# satshakit_FabPCBMaker.net
KiCad netlist of a schematic drawn in EAGLE
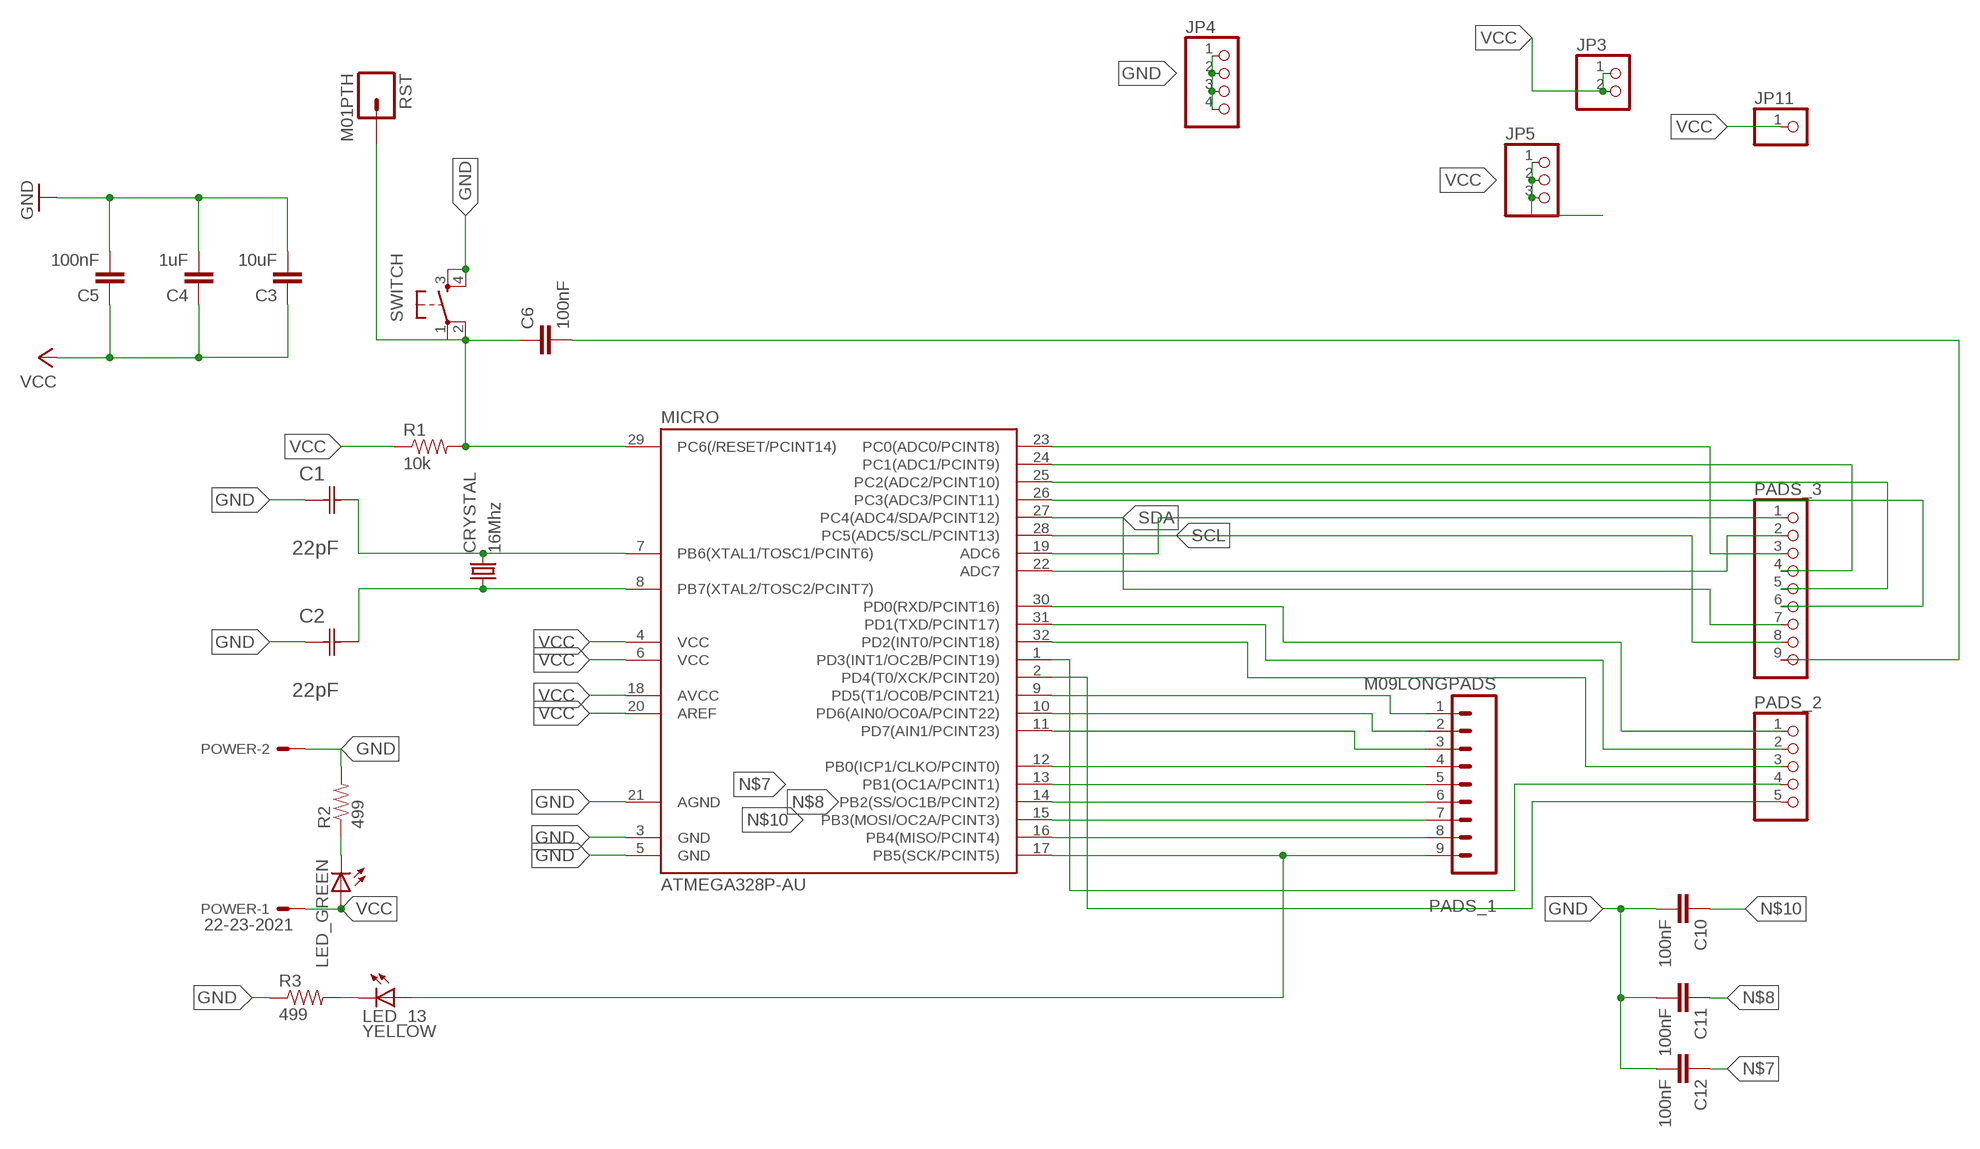
[diagram p0: schematic, sheet 1]

(export (version "E")
  (design (tool "Eeschema 10.0.6"))
  (components
    (comp (ref "C1")
      (value "22pF")
      (footprint "eagle-import:CAPC3216X178N")
      (fields (field (name "MPN") "0612ZC225MAT2A") (field (name "TOLERANCE") "±20%"))
      (libsource (lib "eagle-import") (part "0612ZC225MAT2A"))
    )
    (comp (ref "C2")
      (value "22pF")
      (footprint "eagle-import:CAPC3216X178N")
      (fields (field (name "MPN") "0612ZC225MAT2A") (field (name "TOLERANCE") "±20%"))
      (libsource (lib "eagle-import") (part "0612ZC225MAT2A"))
    )
    (comp (ref "C3")
      (value "10uF")
      (footprint "eagle-import:1206")
      (libsource (lib "eagle-import") (part "CAP1206"))
    )
    (comp (ref "C4")
      (value "1uF")
      (footprint "eagle-import:1206")
      (libsource (lib "eagle-import") (part "CAP1206"))
    )
    (comp (ref "C5")
      (value "100nF")
      (footprint "eagle-import:1206")
      (libsource (lib "eagle-import") (part "CAP1206"))
    )
    (comp (ref "C6")
      (value "100nF")
      (footprint "eagle-import:1206")
      (libsource (lib "eagle-import") (part "CAP1206"))
    )
    (comp (ref "C10")
      (value "100nF")
      (footprint "eagle-import:1206")
      (libsource (lib "eagle-import") (part "CAP1206"))
    )
    (comp (ref "C11")
      (value "100nF")
      (footprint "eagle-import:1206")
      (libsource (lib "eagle-import") (part "CAP1206"))
    )
    (comp (ref "C12")
      (value "100nF")
      (footprint "eagle-import:1206")
      (libsource (lib "eagle-import") (part "CAP1206"))
    )
    (comp (ref "CRYSTAL")
      (value "16Mhz")
      (footprint "eagle-import:CSM-7X-DU")
      (libsource (lib "eagle-import") (part "CSM-7X-DU"))
    )
    (comp (ref "JP3")
      (value "PINHD-1X2")
      (footprint "eagle-import:1X02")
      (libsource (lib "eagle-import") (part "PINHD-1X2"))
    )
    (comp (ref "JP4")
      (value "PINHD-1X4")
      (footprint "eagle-import:1X04")
      (libsource (lib "eagle-import") (part "PINHD-1X4"))
    )
    (comp (ref "JP5")
      (value "PINHD-1X3")
      (footprint "eagle-import:1X03")
      (libsource (lib "eagle-import") (part "PINHD-1X3"))
    )
    (comp (ref "JP11")
      (value "PINHD-1X1")
      (footprint "eagle-import:1X01")
      (libsource (lib "eagle-import") (part "PINHD-1X1"))
    )
    (comp (ref "LED_13")
      (value "YELLOW")
      (footprint "eagle-import:1206")
      (libsource (lib "eagle-import") (part "LED1206"))
    )
    (comp (ref "LED_GREEN")
      (value "LED1206")
      (footprint "eagle-import:1206")
      (libsource (lib "eagle-import") (part "LED1206"))
    )
    (comp (ref "MICRO")
      (value "ATMEGA328P-AU")
      (footprint "eagle-import:TQFP32-08")
      (libsource (lib "eagle-import") (part "ATMEGA48/88/168-AU"))
    )
    (comp (ref "PADS_1")
      (value "M09LONGPADS")
      (footprint "eagle-import:1X09_LONGPADS")
      (libsource (lib "eagle-import") (part "M09LONGPADS"))
    )
    (comp (ref "PADS_2")
      (value "PINHD-1X5")
      (footprint "eagle-import:1X05")
      (libsource (lib "eagle-import") (part "PINHD-1X5"))
    )
    (comp (ref "PADS_3")
      (value "PINHD-1X9")
      (footprint "eagle-import:1X09")
      (libsource (lib "eagle-import") (part "PINHD-1X9"))
    )
    (comp (ref "POWER")
      (value "22-23-2021")
      (footprint "eagle-import:22-23-2021")
      (fields (field (name "MF") "MOLEX"))
      (libsource (lib "eagle-import") (part "22-23-2021"))
    )
    (comp (ref "R1")
      (value "10k")
      (footprint "eagle-import:1206")
      (libsource (lib "eagle-import") (part "RESISTOR1206"))
    )
    (comp (ref "R2")
      (value "499")
      (footprint "eagle-import:1206")
      (libsource (lib "eagle-import") (part "RESISTOR1206"))
    )
    (comp (ref "R3")
      (value "499")
      (footprint "eagle-import:1206")
      (libsource (lib "eagle-import") (part "RESISTOR1206"))
    )
    (comp (ref "RST")
      (value "M01PTH")
      (footprint "eagle-import:1X01")
      (libsource (lib "eagle-import") (part "M01PTH"))
    )
    (comp (ref "SWITCH")
      (value "6MM_SWITCH6MM_SWITCH")
      (footprint "eagle-import:6MM_SWITCH")
      (libsource (lib "eagle-import") (part "6MM_SWITCH6MM_SWITCH"))
    )
  )
  (nets
    (net (code "1") (name "GND") (class "Default")
      (node (ref "C1") (pin "1") (pinfunction "C1_1") (pintype "passive"))
      (node (ref "C10") (pin "2") (pinfunction "2_2") (pintype "passive"))
      (node (ref "C11") (pin "2") (pinfunction "2_2") (pintype "passive"))
      (node (ref "C12") (pin "2") (pinfunction "2_2") (pintype "passive"))
      (node (ref "C2") (pin "1") (pinfunction "C1_1") (pintype "passive"))
      (node (ref "C3") (pin "2") (pinfunction "2_2") (pintype "passive"))
      (node (ref "C4") (pin "2") (pinfunction "2_2") (pintype "passive"))
      (node (ref "C5") (pin "2") (pinfunction "2_2") (pintype "passive"))
      (node (ref "JP4") (pin "1") (pinfunction "1_1") (pintype "passive"))
      (node (ref "JP4") (pin "2") (pinfunction "2_2") (pintype "passive"))
      (node (ref "JP4") (pin "3") (pinfunction "3_3") (pintype "passive"))
      (node (ref "JP4") (pin "4") (pinfunction "4_4") (pintype "passive"))
      (node (ref "MICRO") (pin "21") (pinfunction "AGND_21") (pintype "power_in"))
      (node (ref "MICRO") (pin "3") (pinfunction "GND_3") (pintype "power_in"))
      (node (ref "MICRO") (pin "5") (pinfunction "GND_5") (pintype "power_in"))
      (node (ref "POWER") (pin "2") (pinfunction "S_2") (pintype "passive"))
      (node (ref "R2") (pin "2") (pinfunction "2_2") (pintype "passive"))
      (node (ref "R3") (pin "1") (pinfunction "1_1") (pintype "passive"))
      (node (ref "SWITCH") (pin "3") (pinfunction "S_3") (pintype "passive"))
      (node (ref "SWITCH") (pin "4") (pinfunction "S1_4") (pintype "passive"))
    )
    (net (code "2") (name "N$7") (class "Default")
      (node (ref "C12") (pin "1") (pinfunction "1_1") (pintype "passive"))
      (node (ref "MICRO") (pin "13") (pinfunction "PB1(OC1A/PCINT1)_13") (pintype "bidirectional"))
      (node (ref "PADS_1") (pin "5") (pinfunction "5_5") (pintype "passive"))
    )
    (net (code "3") (name "N$8") (class "Default")
      (node (ref "C11") (pin "1") (pinfunction "1_1") (pintype "passive"))
      (node (ref "MICRO") (pin "14") (pinfunction "PB2(SS/OC1B/PCINT2)_14") (pintype "bidirectional"))
      (node (ref "PADS_1") (pin "6") (pinfunction "6_6") (pintype "passive"))
    )
    (net (code "4") (name "N$10") (class "Default")
      (node (ref "C10") (pin "1") (pinfunction "1_1") (pintype "passive"))
      (node (ref "MICRO") (pin "15") (pinfunction "PB3(MOSI/OC2A/PCINT3)_15") (pintype "bidirectional"))
      (node (ref "PADS_1") (pin "7") (pinfunction "7_7") (pintype "passive"))
    )
    (net (code "5") (name "Net-(C1-C2)") (class "Default")
      (node (ref "C1") (pin "2") (pinfunction "C2_2") (pintype "passive"))
      (node (ref "CRYSTAL") (pin "2") (pinfunction "2_2") (pintype "passive"))
      (node (ref "MICRO") (pin "7") (pinfunction "PB6(XTAL1/TOSC1/PCINT6)_7") (pintype "bidirectional"))
    )
    (net (code "6") (name "Net-(C2-C2)") (class "Default")
      (node (ref "C2") (pin "2") (pinfunction "C2_2") (pintype "passive"))
      (node (ref "CRYSTAL") (pin "1") (pinfunction "1_1") (pintype "passive"))
      (node (ref "MICRO") (pin "8") (pinfunction "PB7(XTAL2/TOSC2/PCINT7)_8") (pintype "bidirectional"))
    )
    (net (code "7") (name "Net-(C6-Pad2)") (class "Default")
      (node (ref "C6") (pin "2") (pinfunction "2_2") (pintype "passive"))
      (node (ref "PADS_3") (pin "9") (pinfunction "9_9") (pintype "passive"))
    )
    (net (code "8") (name "Net-(LED_13-A)") (class "Default")
      (node (ref "LED_13") (pin "1") (pinfunction "A_1") (pintype "passive"))
      (node (ref "MICRO") (pin "17") (pinfunction "PB5(SCK/PCINT5)_17") (pintype "bidirectional"))
      (node (ref "PADS_1") (pin "9") (pinfunction "9_9") (pintype "passive"))
    )
    (net (code "9") (name "Net-(LED_13-C)") (class "Default")
      (node (ref "LED_13") (pin "2") (pinfunction "C_2") (pintype "passive"))
      (node (ref "R3") (pin "2") (pinfunction "2_2") (pintype "passive"))
    )
    (net (code "10") (name "Net-(LED_GREEN-C)") (class "Default")
      (node (ref "LED_GREEN") (pin "2") (pinfunction "C_2") (pintype "passive"))
      (node (ref "R2") (pin "1") (pinfunction "1_1") (pintype "passive"))
    )
    (net (code "11") (name "Net-(MICRO-ADC6)") (class "Default")
      (node (ref "MICRO") (pin "19") (pinfunction "ADC6_19") (pintype "passive"))
      (node (ref "PADS_3") (pin "1") (pinfunction "1_1") (pintype "passive"))
    )
    (net (code "12") (name "Net-(MICRO-ADC7)") (class "Default")
      (node (ref "MICRO") (pin "22") (pinfunction "ADC7_22") (pintype "passive"))
      (node (ref "PADS_3") (pin "2") (pinfunction "2_2") (pintype "passive"))
    )
    (net (code "13") (name "Net-(MICRO-PB0(ICP1{slash}CLKO{slash}PCINT0))") (class "Default")
      (node (ref "MICRO") (pin "12") (pinfunction "PB0(ICP1/CLKO/PCINT0)_12") (pintype "bidirectional"))
      (node (ref "PADS_1") (pin "4") (pinfunction "4_4") (pintype "passive"))
    )
    (net (code "14") (name "Net-(MICRO-PB4(MISO{slash}PCINT4))") (class "Default")
      (node (ref "MICRO") (pin "16") (pinfunction "PB4(MISO/PCINT4)_16") (pintype "bidirectional"))
      (node (ref "PADS_1") (pin "8") (pinfunction "8_8") (pintype "passive"))
    )
    (net (code "15") (name "Net-(MICRO-PC0(ADC0{slash}PCINT8))") (class "Default")
      (node (ref "MICRO") (pin "23") (pinfunction "PC0(ADC0/PCINT8)_23") (pintype "bidirectional"))
      (node (ref "PADS_3") (pin "3") (pinfunction "3_3") (pintype "passive"))
    )
    (net (code "16") (name "Net-(MICRO-PC1(ADC1{slash}PCINT9))") (class "Default")
      (node (ref "MICRO") (pin "24") (pinfunction "PC1(ADC1/PCINT9)_24") (pintype "bidirectional"))
      (node (ref "PADS_3") (pin "4") (pinfunction "4_4") (pintype "passive"))
    )
    (net (code "17") (name "Net-(MICRO-PC2(ADC2{slash}PCINT10))") (class "Default")
      (node (ref "MICRO") (pin "25") (pinfunction "PC2(ADC2/PCINT10)_25") (pintype "bidirectional"))
      (node (ref "PADS_3") (pin "5") (pinfunction "5_5") (pintype "passive"))
    )
    (net (code "18") (name "Net-(MICRO-PC3(ADC3{slash}PCINT11))") (class "Default")
      (node (ref "MICRO") (pin "26") (pinfunction "PC3(ADC3/PCINT11)_26") (pintype "bidirectional"))
      (node (ref "PADS_3") (pin "6") (pinfunction "6_6") (pintype "passive"))
    )
    (net (code "19") (name "Net-(MICRO-PC6({slash}RESET{slash}PCINT14))") (class "Default")
      (node (ref "C6") (pin "1") (pinfunction "1_1") (pintype "passive"))
      (node (ref "MICRO") (pin "29") (pinfunction "PC6(/RESET/PCINT14)_29") (pintype "bidirectional"))
      (node (ref "R1") (pin "2") (pinfunction "2_2") (pintype "passive"))
      (node (ref "RST") (pin "1") (pinfunction "1_1") (pintype "passive"))
      (node (ref "SWITCH") (pin "1") (pinfunction "P_1") (pintype "passive"))
      (node (ref "SWITCH") (pin "2") (pinfunction "P1_2") (pintype "passive"))
    )
    (net (code "20") (name "Net-(MICRO-PD0(RXD{slash}PCINT16))") (class "Default")
      (node (ref "MICRO") (pin "30") (pinfunction "PD0(RXD/PCINT16)_30") (pintype "bidirectional"))
      (node (ref "PADS_2") (pin "1") (pinfunction "1_1") (pintype "passive"))
    )
    (net (code "21") (name "Net-(MICRO-PD1(TXD{slash}PCINT17))") (class "Default")
      (node (ref "MICRO") (pin "31") (pinfunction "PD1(TXD/PCINT17)_31") (pintype "bidirectional"))
      (node (ref "PADS_2") (pin "2") (pinfunction "2_2") (pintype "passive"))
    )
    (net (code "22") (name "Net-(MICRO-PD2(INT0{slash}PCINT18))") (class "Default")
      (node (ref "MICRO") (pin "32") (pinfunction "PD2(INT0/PCINT18)_32") (pintype "bidirectional"))
      (node (ref "PADS_2") (pin "3") (pinfunction "3_3") (pintype "passive"))
    )
    (net (code "23") (name "Net-(MICRO-PD3(INT1{slash}OC2B{slash}PCINT19))") (class "Default")
      (node (ref "MICRO") (pin "1") (pinfunction "PD3(INT1/OC2B/PCINT19)_1") (pintype "bidirectional"))
      (node (ref "PADS_2") (pin "4") (pinfunction "4_4") (pintype "passive"))
    )
    (net (code "24") (name "Net-(MICRO-PD4(T0{slash}XCK{slash}PCINT20))") (class "Default")
      (node (ref "MICRO") (pin "2") (pinfunction "PD4(T0/XCK/PCINT20)_2") (pintype "bidirectional"))
      (node (ref "PADS_2") (pin "5") (pinfunction "5_5") (pintype "passive"))
    )
    (net (code "25") (name "Net-(MICRO-PD5(T1{slash}OC0B{slash}PCINT21))") (class "Default")
      (node (ref "MICRO") (pin "9") (pinfunction "PD5(T1/OC0B/PCINT21)_9") (pintype "bidirectional"))
      (node (ref "PADS_1") (pin "1") (pinfunction "1_1") (pintype "passive"))
    )
    (net (code "26") (name "Net-(MICRO-PD6(AIN0{slash}OC0A{slash}PCINT22))") (class "Default")
      (node (ref "MICRO") (pin "10") (pinfunction "PD6(AIN0/OC0A/PCINT22)_10") (pintype "bidirectional"))
      (node (ref "PADS_1") (pin "2") (pinfunction "2_2") (pintype "passive"))
    )
    (net (code "27") (name "Net-(MICRO-PD7(AIN1{slash}PCINT23))") (class "Default")
      (node (ref "MICRO") (pin "11") (pinfunction "PD7(AIN1/PCINT23)_11") (pintype "bidirectional"))
      (node (ref "PADS_1") (pin "3") (pinfunction "3_3") (pintype "passive"))
    )
    (net (code "28") (name "SCL") (class "Default")
      (node (ref "MICRO") (pin "28") (pinfunction "PC5(ADC5/SCL/PCINT13)_28") (pintype "bidirectional"))
      (node (ref "PADS_3") (pin "8") (pinfunction "8_8") (pintype "passive"))
    )
    (net (code "29") (name "SDA") (class "Default")
      (node (ref "MICRO") (pin "27") (pinfunction "PC4(ADC4/SDA/PCINT12)_27") (pintype "bidirectional"))
      (node (ref "PADS_3") (pin "7") (pinfunction "7_7") (pintype "passive"))
    )
    (net (code "30") (name "VCC") (class "Default")
      (node (ref "C3") (pin "1") (pinfunction "1_1") (pintype "passive"))
      (node (ref "C4") (pin "1") (pinfunction "1_1") (pintype "passive"))
      (node (ref "C5") (pin "1") (pinfunction "1_1") (pintype "passive"))
      (node (ref "JP11") (pin "1") (pinfunction "1_1") (pintype "passive"))
      (node (ref "JP3") (pin "1") (pinfunction "1_1") (pintype "passive"))
      (node (ref "JP3") (pin "2") (pinfunction "2_2") (pintype "passive"))
      (node (ref "JP5") (pin "1") (pinfunction "1_1") (pintype "passive"))
      (node (ref "JP5") (pin "2") (pinfunction "2_2") (pintype "passive"))
      (node (ref "JP5") (pin "3") (pinfunction "3_3") (pintype "passive"))
      (node (ref "LED_GREEN") (pin "1") (pinfunction "A_1") (pintype "passive"))
      (node (ref "MICRO") (pin "18") (pinfunction "AVCC_18") (pintype "passive"))
      (node (ref "MICRO") (pin "20") (pinfunction "AREF_20") (pintype "passive"))
      (node (ref "MICRO") (pin "4") (pinfunction "VCC_4") (pintype "power_in"))
      (node (ref "MICRO") (pin "6") (pinfunction "VCC_6") (pintype "power_in"))
      (node (ref "POWER") (pin "1") (pinfunction "S_1") (pintype "passive"))
      (node (ref "R1") (pin "1") (pinfunction "1_1") (pintype "passive"))
    )
  )
)
